# cBlocks_Board_E7_EFS_2v0.net
KiCad netlist of a schematic drawn in EAGLE
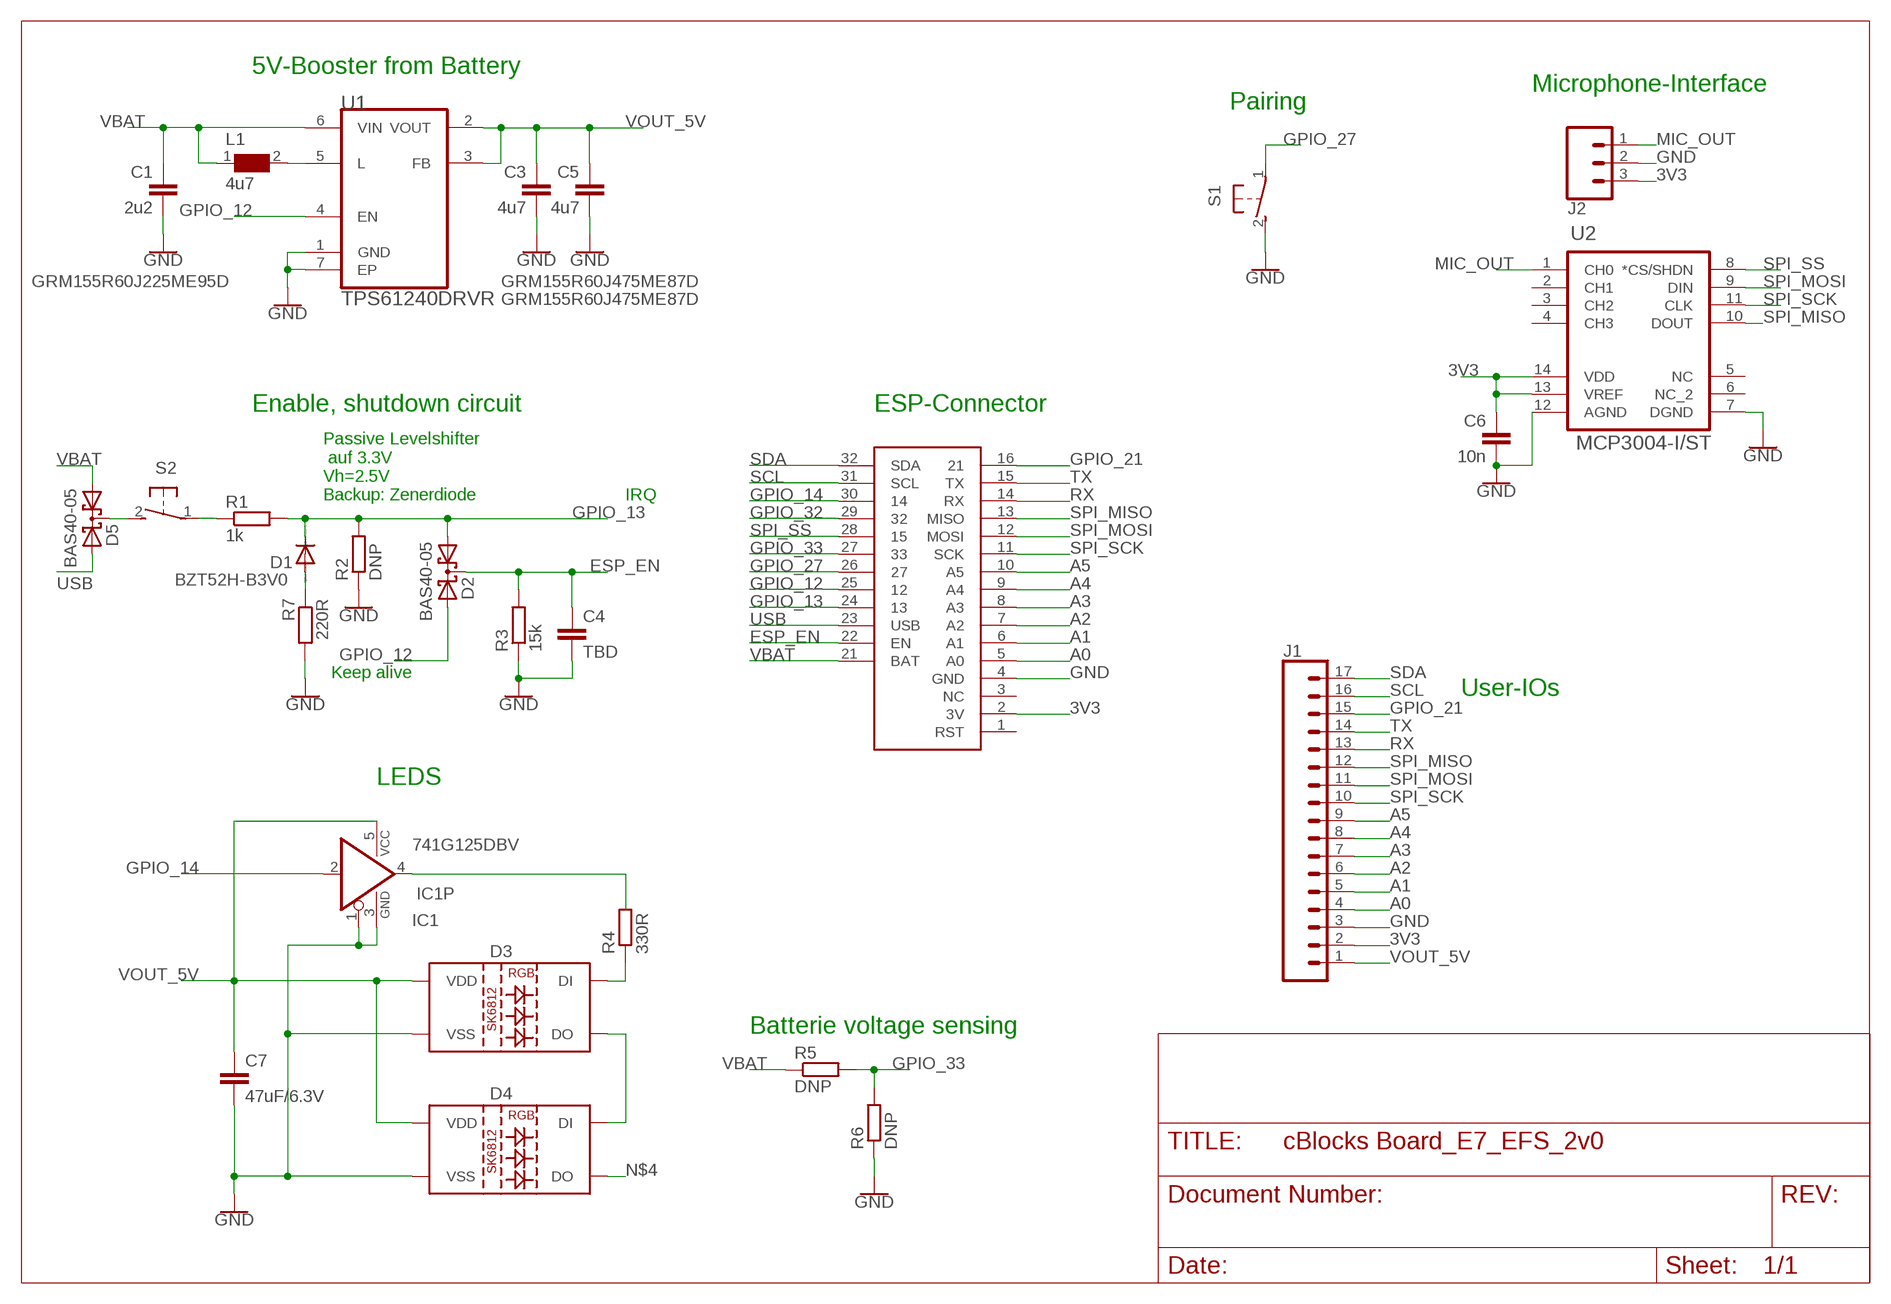
[diagram p0: schematic, sheet 1]

(export (version "E")
  (design (tool "Eeschema 10.0.6"))
  (components
    (comp (ref "C1")
      (value "2u2")
      (footprint "eagle-import:C0402K")
      (fields (field (name "OC_MFG") "GRM155R60J225ME95D "))
      (libsource (lib "eagle-import") (part "resistor_C-EUC0402K"))
    )
    (comp (ref "C3")
      (value "4u7")
      (footprint "eagle-import:C0402K")
      (fields (field (name "OC_MFG") "GRM155R60J475ME87D "))
      (libsource (lib "eagle-import") (part "resistor_C-EUC0402K"))
    )
    (comp (ref "C4")
      (value "TBD")
      (footprint "eagle-import:C0805")
      (libsource (lib "eagle-import") (part "resistor_C-EUC0805"))
    )
    (comp (ref "C5")
      (value "4u7")
      (footprint "eagle-import:C0402K")
      (fields (field (name "OC_MFG") "GRM155R60J475ME87D "))
      (libsource (lib "eagle-import") (part "resistor_C-EUC0402K"))
    )
    (comp (ref "C6")
      (value "10n")
      (footprint "eagle-import:C0805")
      (libsource (lib "eagle-import") (part "resistor_C-EUC0805"))
    )
    (comp (ref "C7")
      (value "47uF/6.3V")
      (footprint "eagle-import:C1206K")
      (libsource (lib "eagle-import") (part "C-EUC1206K"))
    )
    (comp (ref "D1")
      (value "BZT52H-B3V0")
      (footprint "eagle-import:SOD123")
      (libsource (lib "eagle-import") (part "DIODE-SOD123"))
    )
    (comp (ref "D2")
      (value "BAS40-05")
      (footprint "eagle-import:SOT23")
      (libsource (lib "eagle-import") (part "BAS40-05"))
    )
    (comp (ref "D3")
      (value "SK2812SIDE")
      (footprint "eagle-import:SK2812SIDE")
      (libsource (lib "eagle-import") (part "SK2812SIDE"))
    )
    (comp (ref "D4")
      (value "SK2812SIDE")
      (footprint "eagle-import:SK2812SIDE")
      (libsource (lib "eagle-import") (part "SK2812SIDE"))
    )
    (comp (ref "D5")
      (value "BAS40-05")
      (footprint "eagle-import:SOT23")
      (libsource (lib "eagle-import") (part "BAS40-05"))
    )
    (comp (ref "IC1")
      (value "741G125DBV")
      (footprint "eagle-import:SOT353")
      (libsource (lib "eagle-import") (part "741G125DBV"))
    )
    (comp (ref "IC2")
      (value "FEATHERESP32")
      (footprint "eagle-import:FEATHERESP32")
      (libsource (lib "eagle-import") (part "FEATHERESP32"))
    )
    (comp (ref "J1")
      (value "CONN_17")
      (footprint "eagle-import:1X17")
      (libsource (lib "eagle-import") (part "CONN_17"))
    )
    (comp (ref "J2")
      (value "CONN_03")
      (footprint "eagle-import:1X03")
      (libsource (lib "eagle-import") (part "CONN_03"))
    )
    (comp (ref "L1")
      (value "4u7")
      (footprint "eagle-import:WE-PMI_0806")
      (fields (field (name "MPN") "74479776247"))
      (libsource (lib "eagle-import") (part "WE-PMI_0806-74479776247"))
    )
    (comp (ref "R1")
      (value "1k")
      (footprint "eagle-import:R0805")
      (libsource (lib "eagle-import") (part "R-EU_R0805"))
    )
    (comp (ref "R2")
      (value "DNP")
      (footprint "eagle-import:R0805")
      (libsource (lib "eagle-import") (part "R-EU_R0805"))
    )
    (comp (ref "R3")
      (value "15k")
      (footprint "eagle-import:R0805")
      (libsource (lib "eagle-import") (part "R-EU_R0805"))
    )
    (comp (ref "R4")
      (value "330R")
      (footprint "eagle-import:R0805")
      (libsource (lib "eagle-import") (part "R-EU_R0805"))
    )
    (comp (ref "R5")
      (value "DNP")
      (footprint "eagle-import:R0805")
      (libsource (lib "eagle-import") (part "R-EU_R0805"))
    )
    (comp (ref "R6")
      (value "DNP")
      (footprint "eagle-import:R0805")
      (libsource (lib "eagle-import") (part "R-EU_R0805"))
    )
    (comp (ref "R7")
      (value "220R")
      (footprint "eagle-import:R0805")
      (libsource (lib "eagle-import") (part "R-EU_R0805"))
    )
    (comp (ref "S1")
      (value "31-XX")
      (footprint "eagle-import:B3F-31XX")
      (fields
        (field (name "MPN") "B3F-3100")
        (field (name "MPN_1") "B3F-3120")
        (field (name "OC_FARNELL") "1608275")
      )
      (libsource (lib "eagle-import") (part "31-XX"))
    )
    (comp (ref "S2")
      (value "31-XX")
      (footprint "eagle-import:B3F-31XX")
      (fields
        (field (name "MPN") "B3F-3100")
        (field (name "MPN_1") "B3F-3120")
        (field (name "OC_FARNELL") "1608275")
      )
      (libsource (lib "eagle-import") (part "31-XX"))
    )
    (comp (ref "U1")
      (value "TPS61240DRVR")
      (footprint "eagle-import:SON65P200X200X80-7N")
      (libsource (lib "eagle-import") (part "TPS61240DRVR"))
    )
    (comp (ref "U2")
      (value "MCP3004-I/ST")
      (footprint "eagle-import:SO14")
      (libsource (lib "eagle-import") (part "MCP3004-I/ST"))
    )
  )
  (nets
    (net (code "1") (name "/3V3") (class "Default")
      (node (ref "C6") (pin "1") (pinfunction "1_1") (pintype "passive"))
      (node (ref "IC2") (pin "2") (pinfunction "3V_2") (pintype "bidirectional"))
      (node (ref "J1") (pin "2") (pinfunction "2_2") (pintype "passive"))
      (node (ref "J2") (pin "3") (pinfunction "3_3") (pintype "passive"))
      (node (ref "U2") (pin "13") (pinfunction "VREF_13") (pintype "input"))
      (node (ref "U2") (pin "14") (pinfunction "VDD_14") (pintype "power_in"))
    )
    (net (code "2") (name "/A0") (class "Default")
      (node (ref "IC2") (pin "5") (pinfunction "A0_5") (pintype "bidirectional"))
      (node (ref "J1") (pin "4") (pinfunction "4_4") (pintype "passive"))
    )
    (net (code "3") (name "/A1") (class "Default")
      (node (ref "IC2") (pin "6") (pinfunction "A1_6") (pintype "bidirectional"))
      (node (ref "J1") (pin "5") (pinfunction "5_5") (pintype "passive"))
    )
    (net (code "4") (name "/A2") (class "Default")
      (node (ref "IC2") (pin "7") (pinfunction "A2_7") (pintype "bidirectional"))
      (node (ref "J1") (pin "6") (pinfunction "6_6") (pintype "passive"))
    )
    (net (code "5") (name "/A3") (class "Default")
      (node (ref "IC2") (pin "8") (pinfunction "A3_8") (pintype "bidirectional"))
      (node (ref "J1") (pin "7") (pinfunction "7_7") (pintype "passive"))
    )
    (net (code "6") (name "/A4") (class "Default")
      (node (ref "IC2") (pin "9") (pinfunction "A4_9") (pintype "bidirectional"))
      (node (ref "J1") (pin "8") (pinfunction "8_8") (pintype "passive"))
    )
    (net (code "7") (name "/A5") (class "Default")
      (node (ref "IC2") (pin "10") (pinfunction "A5_10") (pintype "bidirectional"))
      (node (ref "J1") (pin "9") (pinfunction "9_9") (pintype "passive"))
    )
    (net (code "8") (name "/ESP_EN") (class "Default")
      (node (ref "C4") (pin "1") (pinfunction "1_1") (pintype "passive"))
      (node (ref "D2") (pin "3") (pinfunction "C_3") (pintype "passive"))
      (node (ref "IC2") (pin "22") (pinfunction "EN_22") (pintype "bidirectional"))
      (node (ref "R3") (pin "2") (pinfunction "2_2") (pintype "passive"))
    )
    (net (code "9") (name "/GPIO_12") (class "Default")
      (node (ref "D2") (pin "2") (pinfunction "A2_2") (pintype "passive"))
      (node (ref "IC2") (pin "25") (pinfunction "12_25") (pintype "bidirectional"))
      (node (ref "U1") (pin "4") (pinfunction "EN_4") (pintype "input"))
    )
    (net (code "10") (name "/GPIO_13") (class "Default")
      (node (ref "D1") (pin "C") (pinfunction "C_C") (pintype "passive"))
      (node (ref "D2") (pin "1") (pinfunction "A1_1") (pintype "passive"))
      (node (ref "IC2") (pin "24") (pinfunction "13_24") (pintype "bidirectional"))
      (node (ref "R1") (pin "2") (pinfunction "2_2") (pintype "passive"))
      (node (ref "R2") (pin "2") (pinfunction "2_2") (pintype "passive"))
    )
    (net (code "11") (name "/GPIO_14") (class "Default")
      (node (ref "IC1") (pin "2") (pinfunction "I_2") (pintype "input"))
      (node (ref "IC2") (pin "30") (pinfunction "14_30") (pintype "bidirectional"))
    )
    (net (code "12") (name "/GPIO_21") (class "Default")
      (node (ref "IC2") (pin "16") (pinfunction "21_16") (pintype "bidirectional"))
      (node (ref "J1") (pin "15") (pinfunction "15_15") (pintype "passive"))
    )
    (net (code "13") (name "/GPIO_27") (class "Default")
      (node (ref "IC2") (pin "26") (pinfunction "27_26") (pintype "bidirectional"))
      (node (ref "S1") (pin "1") (pinfunction "P_1") (pintype "passive"))
    )
    (net (code "14") (name "/GPIO_32") (class "Default")
      (node (ref "IC2") (pin "29") (pinfunction "32_29") (pintype "bidirectional"))
    )
    (net (code "15") (name "/GPIO_33") (class "Default")
      (node (ref "IC2") (pin "27") (pinfunction "33_27") (pintype "bidirectional"))
      (node (ref "R5") (pin "2") (pinfunction "2_2") (pintype "passive"))
      (node (ref "R6") (pin "2") (pinfunction "2_2") (pintype "passive"))
    )
    (net (code "16") (name "/MIC_OUT") (class "Default")
      (node (ref "J2") (pin "1") (pinfunction "1_1") (pintype "passive"))
      (node (ref "U2") (pin "1") (pinfunction "CH0_1") (pintype "input"))
    )
    (net (code "17") (name "/N$4") (class "Default")
      (node (ref "D4") (pin "3") (pinfunction "DO_3") (pintype "bidirectional"))
    )
    (net (code "18") (name "/RX") (class "Default")
      (node (ref "IC2") (pin "14") (pinfunction "RX_14") (pintype "bidirectional"))
      (node (ref "J1") (pin "13") (pinfunction "13_13") (pintype "passive"))
    )
    (net (code "19") (name "/SCL") (class "Default")
      (node (ref "IC2") (pin "31") (pinfunction "SCL_31") (pintype "bidirectional"))
      (node (ref "J1") (pin "16") (pinfunction "16_16") (pintype "passive"))
    )
    (net (code "20") (name "/SDA") (class "Default")
      (node (ref "IC2") (pin "32") (pinfunction "SDA_32") (pintype "bidirectional"))
      (node (ref "J1") (pin "17") (pinfunction "17_17") (pintype "passive"))
    )
    (net (code "21") (name "/SPI_MISO") (class "Default")
      (node (ref "IC2") (pin "13") (pinfunction "MISO_13") (pintype "bidirectional"))
      (node (ref "J1") (pin "12") (pinfunction "12_12") (pintype "passive"))
      (node (ref "U2") (pin "10") (pinfunction "DOUT_10") (pintype "output"))
    )
    (net (code "22") (name "/SPI_MOSI") (class "Default")
      (node (ref "IC2") (pin "12") (pinfunction "MOSI_12") (pintype "bidirectional"))
      (node (ref "J1") (pin "11") (pinfunction "11_11") (pintype "passive"))
      (node (ref "U2") (pin "9") (pinfunction "DIN_9") (pintype "input"))
    )
    (net (code "23") (name "/SPI_SCK") (class "Default")
      (node (ref "IC2") (pin "11") (pinfunction "SCK_11") (pintype "bidirectional"))
      (node (ref "J1") (pin "10") (pinfunction "10_10") (pintype "passive"))
      (node (ref "U2") (pin "11") (pinfunction "CLK_11") (pintype "input"))
    )
    (net (code "24") (name "/SPI_SS") (class "Default")
      (node (ref "IC2") (pin "28") (pinfunction "15_28") (pintype "bidirectional"))
      (node (ref "U2") (pin "8") (pinfunction "*CS/SHDN_8") (pintype "input"))
    )
    (net (code "25") (name "/TX") (class "Default")
      (node (ref "IC2") (pin "15") (pinfunction "TX_15") (pintype "bidirectional"))
      (node (ref "J1") (pin "14") (pinfunction "14_14") (pintype "passive"))
    )
    (net (code "26") (name "/USB") (class "Default")
      (node (ref "D5") (pin "2") (pinfunction "A2_2") (pintype "passive"))
      (node (ref "IC2") (pin "23") (pinfunction "USB_23") (pintype "bidirectional"))
    )
    (net (code "27") (name "/VBAT") (class "Default")
      (node (ref "C1") (pin "1") (pinfunction "1_1") (pintype "passive"))
      (node (ref "D5") (pin "1") (pinfunction "A1_1") (pintype "passive"))
      (node (ref "IC2") (pin "21") (pinfunction "BAT_21") (pintype "bidirectional"))
      (node (ref "L1") (pin "1") (pinfunction "1_1") (pintype "passive"))
      (node (ref "R5") (pin "1") (pinfunction "1_1") (pintype "passive"))
      (node (ref "U1") (pin "6") (pinfunction "VIN_6") (pintype "power_in"))
    )
    (net (code "28") (name "/VOUT_5V") (class "Default")
      (node (ref "C3") (pin "1") (pinfunction "1_1") (pintype "passive"))
      (node (ref "C5") (pin "1") (pinfunction "1_1") (pintype "passive"))
      (node (ref "C7") (pin "1") (pinfunction "1_1") (pintype "passive"))
      (node (ref "D3") (pin "2") (pinfunction "VDD_2") (pintype "bidirectional"))
      (node (ref "D4") (pin "2") (pinfunction "VDD_2") (pintype "bidirectional"))
      (node (ref "IC1") (pin "5") (pinfunction "VCC_5") (pintype "power_in"))
      (node (ref "J1") (pin "1") (pinfunction "1_1") (pintype "passive"))
      (node (ref "U1") (pin "2") (pinfunction "VOUT_2") (pintype "output"))
      (node (ref "U1") (pin "3") (pinfunction "FB_3") (pintype "input"))
    )
    (net (code "29") (name "GND") (class "Default")
      (node (ref "C1") (pin "2") (pinfunction "2_2") (pintype "passive"))
      (node (ref "C3") (pin "2") (pinfunction "2_2") (pintype "passive"))
      (node (ref "C4") (pin "2") (pinfunction "2_2") (pintype "passive"))
      (node (ref "C5") (pin "2") (pinfunction "2_2") (pintype "passive"))
      (node (ref "C6") (pin "2") (pinfunction "2_2") (pintype "passive"))
      (node (ref "C7") (pin "2") (pinfunction "2_2") (pintype "passive"))
      (node (ref "D3") (pin "4") (pinfunction "VSS_4") (pintype "bidirectional"))
      (node (ref "D4") (pin "4") (pinfunction "VSS_4") (pintype "bidirectional"))
      (node (ref "IC1") (pin "1") (pinfunction "OE_1") (pintype "input"))
      (node (ref "IC1") (pin "3") (pinfunction "GND_3") (pintype "power_in"))
      (node (ref "IC2") (pin "4") (pinfunction "GND_4") (pintype "bidirectional"))
      (node (ref "J1") (pin "3") (pinfunction "3_3") (pintype "passive"))
      (node (ref "J2") (pin "2") (pinfunction "2_2") (pintype "passive"))
      (node (ref "R2") (pin "1") (pinfunction "1_1") (pintype "passive"))
      (node (ref "R3") (pin "1") (pinfunction "1_1") (pintype "passive"))
      (node (ref "R6") (pin "1") (pinfunction "1_1") (pintype "passive"))
      (node (ref "R7") (pin "2") (pinfunction "2_2") (pintype "passive"))
      (node (ref "S1") (pin "2") (pinfunction "S_2") (pintype "passive"))
      (node (ref "U1") (pin "1") (pinfunction "GND_1") (pintype "passive"))
      (node (ref "U1") (pin "7") (pinfunction "EP_7") (pintype "passive"))
      (node (ref "U2") (pin "12") (pinfunction "AGND_12") (pintype "passive"))
      (node (ref "U2") (pin "7") (pinfunction "DGND_7") (pintype "passive"))
    )
    (net (code "30") (name "Net-(D1-PadA)") (class "Default")
      (node (ref "D1") (pin "A") (pinfunction "A_A") (pintype "passive"))
      (node (ref "R7") (pin "1") (pinfunction "1_1") (pintype "passive"))
    )
    (net (code "31") (name "Net-(D3-DI)") (class "Default")
      (node (ref "D3") (pin "1") (pinfunction "DI_1") (pintype "bidirectional"))
      (node (ref "R4") (pin "1") (pinfunction "1_1") (pintype "passive"))
    )
    (net (code "32") (name "Net-(D3-DO)") (class "Default")
      (node (ref "D3") (pin "3") (pinfunction "DO_3") (pintype "bidirectional"))
      (node (ref "D4") (pin "1") (pinfunction "DI_1") (pintype "bidirectional"))
    )
    (net (code "33") (name "Net-(D5-C)") (class "Default")
      (node (ref "D5") (pin "3") (pinfunction "C_3") (pintype "passive"))
      (node (ref "S2") (pin "2") (pinfunction "S_2") (pintype "passive"))
    )
    (net (code "34") (name "Net-(IC1A-O)") (class "Default")
      (node (ref "IC1") (pin "4") (pinfunction "O_4") (pintype "tri_state"))
      (node (ref "R4") (pin "2") (pinfunction "2_2") (pintype "passive"))
    )
    (net (code "35") (name "Net-(S2-P)") (class "Default")
      (node (ref "R1") (pin "1") (pinfunction "1_1") (pintype "passive"))
      (node (ref "S2") (pin "1") (pinfunction "P_1") (pintype "passive"))
    )
    (net (code "36") (name "Net-(U1-L)") (class "Default")
      (node (ref "L1") (pin "2") (pinfunction "2_2") (pintype "passive"))
      (node (ref "U1") (pin "5") (pinfunction "L_5") (pintype "input"))
    )
    (net (code "37") (name "unconnected-(IC2-NC-Pad3)") (class "Default")
      (node (ref "IC2") (pin "3") (pinfunction "NC_3") (pintype "bidirectional"))
    )
    (net (code "38") (name "unconnected-(IC2-RST-Pad1)") (class "Default")
      (node (ref "IC2") (pin "1") (pinfunction "RST_1") (pintype "bidirectional"))
    )
    (net (code "39") (name "unconnected-(U2-CH1-Pad2)") (class "Default")
      (node (ref "U2") (pin "2") (pinfunction "CH1_2") (pintype "input"))
    )
    (net (code "40") (name "unconnected-(U2-CH2-Pad3)") (class "Default")
      (node (ref "U2") (pin "3") (pinfunction "CH2_3") (pintype "input"))
    )
    (net (code "41") (name "unconnected-(U2-CH3-Pad4)") (class "Default")
      (node (ref "U2") (pin "4") (pinfunction "CH3_4") (pintype "input"))
    )
    (net (code "42") (name "unconnected-(U2-NC-Pad5)") (class "Default")
      (node (ref "U2") (pin "5") (pinfunction "NC_5") (pintype "no_connect"))
    )
    (net (code "43") (name "unconnected-(U2-NC_2-Pad6)") (class "Default")
      (node (ref "U2") (pin "6") (pinfunction "NC_2_6") (pintype "no_connect"))
    )
  )
)
